# main.net
KiCad netlist of a schematic drawn in EAGLE
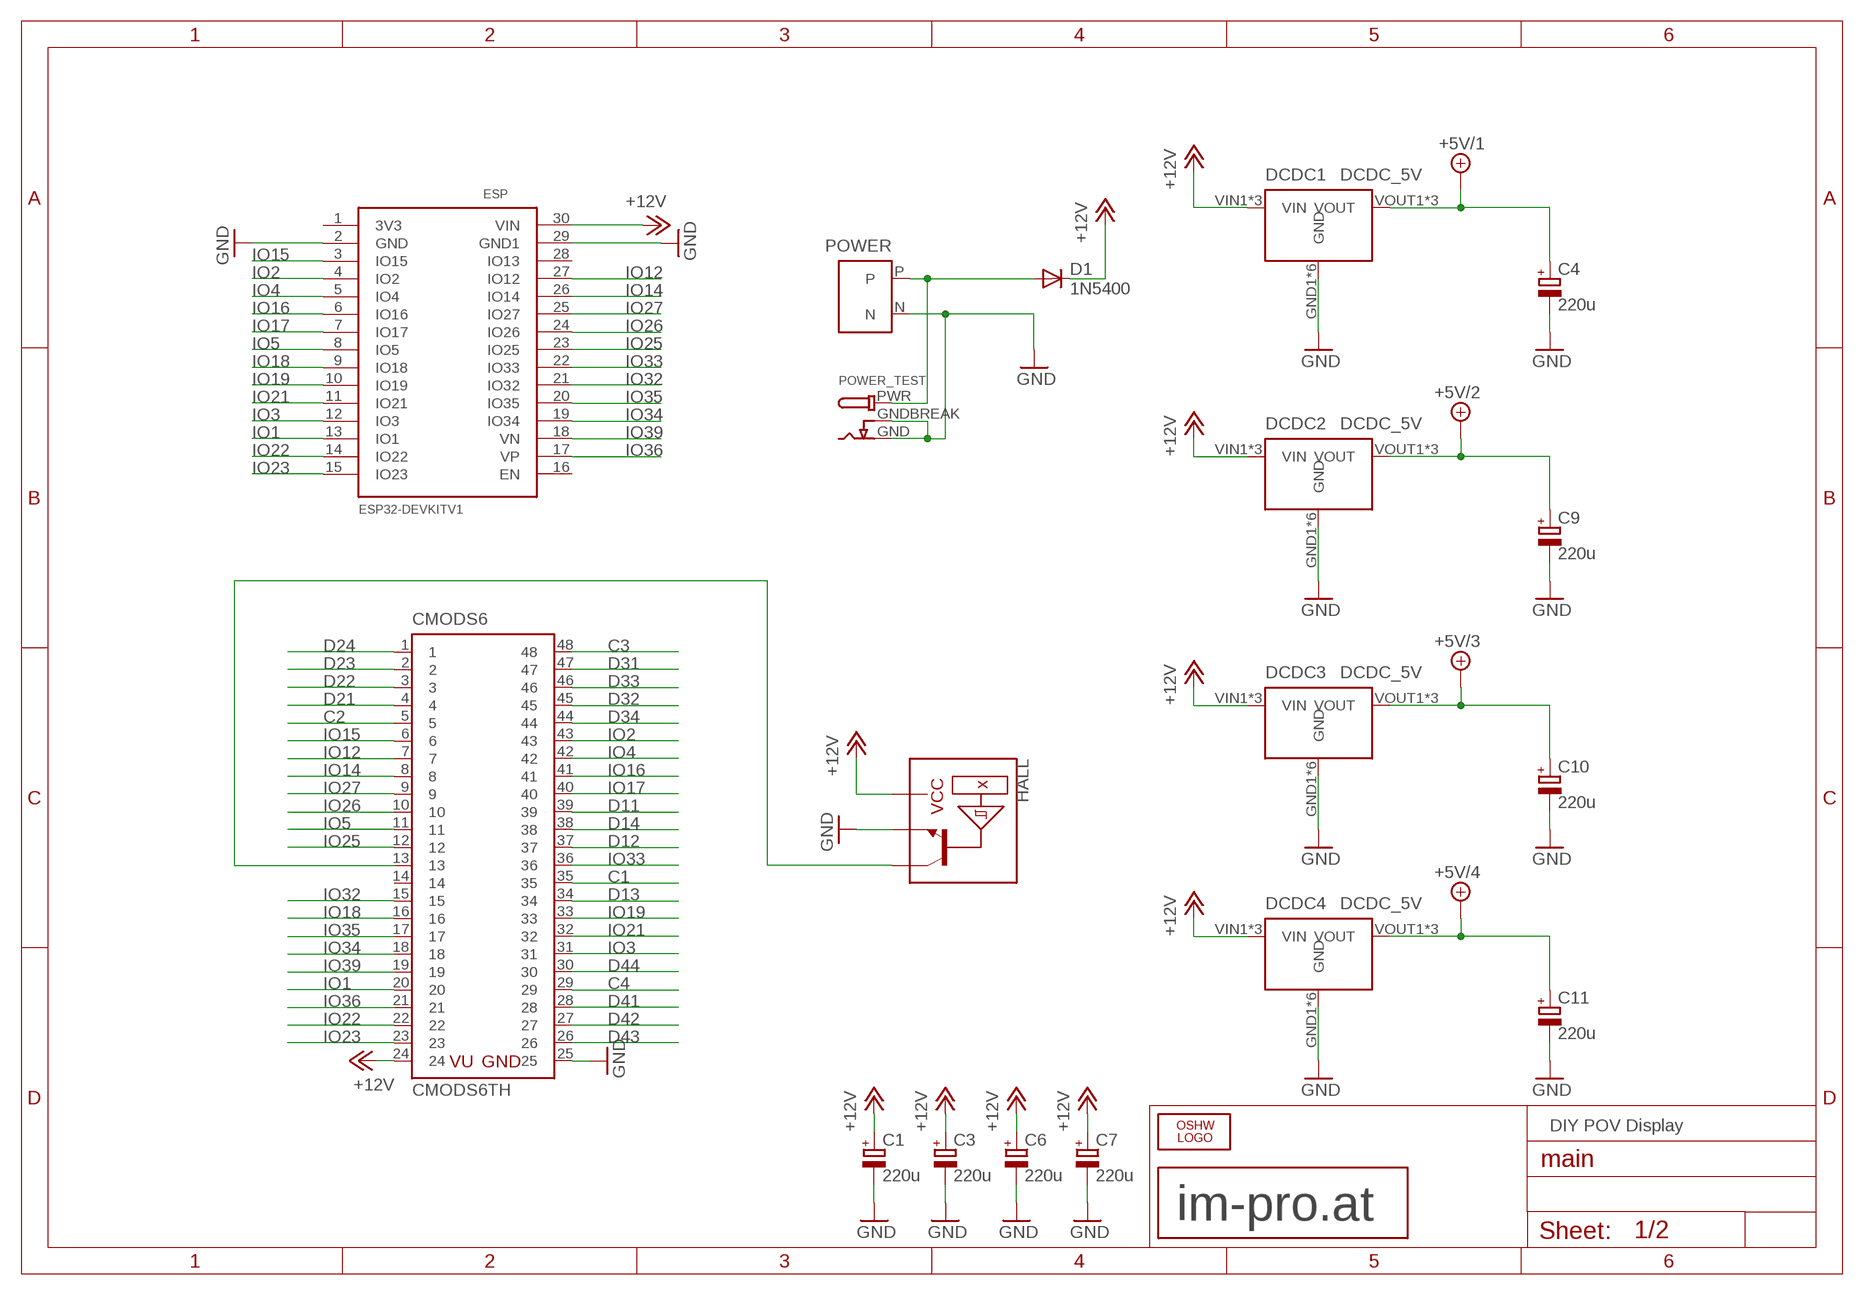
[diagram p0: schematic, sheet 1]
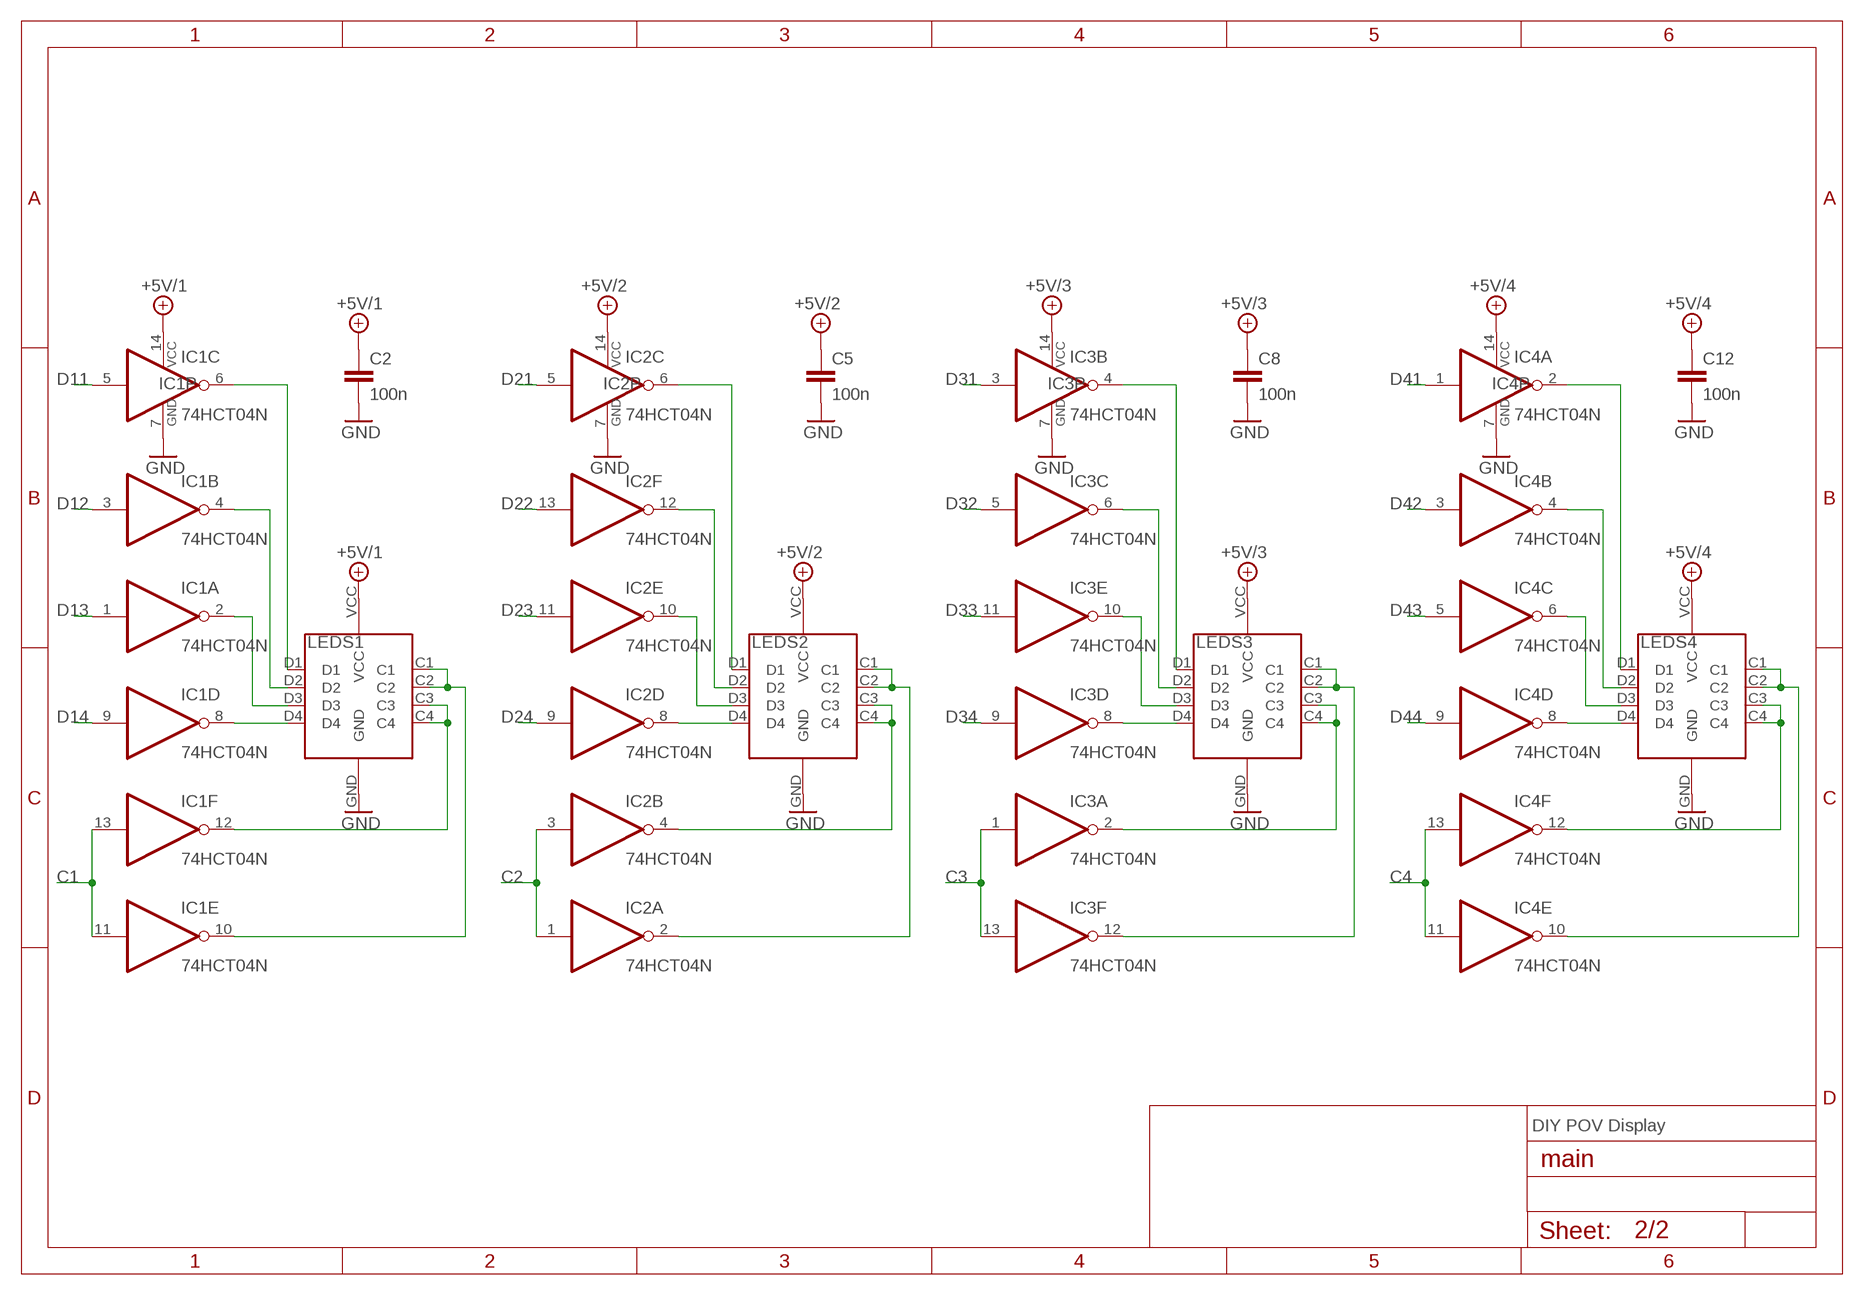
[diagram p1: schematic, sheet 2]

(export (version "E")
  (design (tool "Eeschema 10.0.6"))
  (components
    (comp (ref "C1")
      (value "220u")
      (footprint "eagle-import:E3,5-8")
      (libsource (lib "eagle-import") (part "CPOL-EUE3.5-8"))
    )
    (comp (ref "C3")
      (value "220u")
      (footprint "eagle-import:E3,5-8")
      (libsource (lib "eagle-import") (part "CPOL-EUE3.5-8"))
    )
    (comp (ref "C4")
      (value "220u")
      (footprint "eagle-import:E3,5-8")
      (libsource (lib "eagle-import") (part "CPOL-EUE3.5-8"))
    )
    (comp (ref "C6")
      (value "220u")
      (footprint "eagle-import:E3,5-8")
      (libsource (lib "eagle-import") (part "CPOL-EUE3.5-8"))
    )
    (comp (ref "C7")
      (value "220u")
      (footprint "eagle-import:E3,5-8")
      (libsource (lib "eagle-import") (part "CPOL-EUE3.5-8"))
    )
    (comp (ref "C9")
      (value "220u")
      (footprint "eagle-import:E3,5-8")
      (libsource (lib "eagle-import") (part "CPOL-EUE3.5-8"))
    )
    (comp (ref "C10")
      (value "220u")
      (footprint "eagle-import:E3,5-8")
      (libsource (lib "eagle-import") (part "CPOL-EUE3.5-8"))
    )
    (comp (ref "C11")
      (value "220u")
      (footprint "eagle-import:E3,5-8")
      (libsource (lib "eagle-import") (part "CPOL-EUE3.5-8"))
    )
    (comp (ref "CMODS6")
      (value "CMODS6TH")
      (footprint "eagle-import:DIL48")
      (libsource (lib "eagle-import") (part "CMODS6TH"))
    )
    (comp (ref "D1")
      (value "1N5400")
      (footprint "eagle-import:DO201-15")
      (libsource (lib "eagle-import") (part "1N5400"))
    )
    (comp (ref "DCDC1")
      (value "DCDC_5V")
      (footprint "eagle-import:DCDC")
      (libsource (lib "eagle-import") (part "DCDC_5V"))
    )
    (comp (ref "DCDC2")
      (value "DCDC_5V")
      (footprint "eagle-import:DCDC")
      (libsource (lib "eagle-import") (part "DCDC_5V"))
    )
    (comp (ref "DCDC3")
      (value "DCDC_5V")
      (footprint "eagle-import:DCDC")
      (libsource (lib "eagle-import") (part "DCDC_5V"))
    )
    (comp (ref "DCDC4")
      (value "DCDC_5V")
      (footprint "eagle-import:DCDC")
      (libsource (lib "eagle-import") (part "DCDC_5V"))
    )
    (comp (ref "ESP")
      (value "ESP32DEVKITV1")
      (footprint "eagle-import:ESP32-DEVKITV1")
      (libsource (lib "eagle-import") (part "ESP32DEVKITV1"))
    )
    (comp (ref "HALL")
      (value "HALL")
      (footprint "eagle-import:HALL")
      (libsource (lib "eagle-import") (part "HALL"))
    )
    (comp (ref "LOGO1")
      (value "OSHW_LOGO_FILLX0350-NT")
      (footprint "eagle-import:OSHW_FILLX350_NOTEXT")
      (libsource (lib "eagle-import") (part "OSHW_LOGO_FILLX0350-NT"))
    )
    (comp (ref "POWER")
      (value "TX30")
      (footprint "eagle-import:XT30")
      (libsource (lib "eagle-import") (part "TX30"))
    )
    (comp (ref "POWER_TEST")
      (value "DCBARRELPTH")
      (footprint "eagle-import:DCJACK_2MM_PTH")
      (libsource (lib "eagle-import") (part "DCBARRELPTH"))
    )
    (comp (ref "U$2")
      (value "LOGO20MM")
      (footprint "eagle-import:LOGO_20MM")
      (libsource (lib "eagle-import") (part "LOGO20MM"))
    )
    (comp (ref "C2")
      (value "100n")
      (footprint "eagle-import:C025_050-025X075")
      (libsource (lib "eagle-import") (part "C-EU025_050-025X075"))
    )
    (comp (ref "C5")
      (value "100n")
      (footprint "eagle-import:C025_050-025X075")
      (libsource (lib "eagle-import") (part "C-EU025_050-025X075"))
    )
    (comp (ref "C8")
      (value "100n")
      (footprint "eagle-import:C025_050-025X075")
      (libsource (lib "eagle-import") (part "C-EU025_050-025X075"))
    )
    (comp (ref "C12")
      (value "100n")
      (footprint "eagle-import:C025_050-025X075")
      (libsource (lib "eagle-import") (part "C-EU025_050-025X075"))
    )
    (comp (ref "IC1")
      (value "74HCT04N")
      (footprint "eagle-import:DIL14")
      (libsource (lib "eagle-import") (part "7404NHCT"))
    )
    (comp (ref "IC2")
      (value "74HCT04N")
      (footprint "eagle-import:DIL14")
      (libsource (lib "eagle-import") (part "7404NHCT"))
    )
    (comp (ref "IC3")
      (value "74HCT04N")
      (footprint "eagle-import:DIL14")
      (libsource (lib "eagle-import") (part "7404NHCT"))
    )
    (comp (ref "IC4")
      (value "74HCT04N")
      (footprint "eagle-import:DIL14")
      (libsource (lib "eagle-import") (part "7404NHCT"))
    )
    (comp (ref "LEDS1")
      (value "LEDCON")
      (footprint "eagle-import:LEDCON")
      (libsource (lib "eagle-import") (part "LEDCON"))
    )
    (comp (ref "LEDS2")
      (value "LEDCON")
      (footprint "eagle-import:LEDCON")
      (libsource (lib "eagle-import") (part "LEDCON"))
    )
    (comp (ref "LEDS3")
      (value "LEDCON")
      (footprint "eagle-import:LEDCON")
      (libsource (lib "eagle-import") (part "LEDCON"))
    )
    (comp (ref "LEDS4")
      (value "LEDCON")
      (footprint "eagle-import:LEDCON")
      (libsource (lib "eagle-import") (part "LEDCON"))
    )
  )
  (nets
    (net (code "1") (name "+5V{slash}1") (class "Default")
      (node (ref "C2") (pin "1") (pinfunction "1_1") (pintype "passive"))
      (node (ref "C4") (pin "+") (pinfunction "+_+") (pintype "passive"))
      (node (ref "DCDC1") (pin "VOUT1") (pinfunction "VOUT_VOUT1") (pintype "power_in"))
      (node (ref "DCDC1") (pin "VOUT2") (pinfunction "VOUT_VOUT2") (pintype "power_in"))
      (node (ref "DCDC1") (pin "VOUT3") (pinfunction "VOUT_VOUT3") (pintype "power_in"))
      (node (ref "IC1") (pin "14") (pinfunction "VCC_14") (pintype "power_in"))
      (node (ref "LEDS1") (pin "VCC") (pinfunction "VCC_VCC") (pintype "bidirectional"))
    )
    (net (code "2") (name "+5V{slash}2") (class "Default")
      (node (ref "C5") (pin "1") (pinfunction "1_1") (pintype "passive"))
      (node (ref "C9") (pin "+") (pinfunction "+_+") (pintype "passive"))
      (node (ref "DCDC2") (pin "VOUT1") (pinfunction "VOUT_VOUT1") (pintype "power_in"))
      (node (ref "DCDC2") (pin "VOUT2") (pinfunction "VOUT_VOUT2") (pintype "power_in"))
      (node (ref "DCDC2") (pin "VOUT3") (pinfunction "VOUT_VOUT3") (pintype "power_in"))
      (node (ref "IC2") (pin "14") (pinfunction "VCC_14") (pintype "power_in"))
      (node (ref "LEDS2") (pin "VCC") (pinfunction "VCC_VCC") (pintype "bidirectional"))
    )
    (net (code "3") (name "+5V{slash}3") (class "Default")
      (node (ref "C10") (pin "+") (pinfunction "+_+") (pintype "passive"))
      (node (ref "C8") (pin "1") (pinfunction "1_1") (pintype "passive"))
      (node (ref "DCDC3") (pin "VOUT1") (pinfunction "VOUT_VOUT1") (pintype "power_in"))
      (node (ref "DCDC3") (pin "VOUT2") (pinfunction "VOUT_VOUT2") (pintype "power_in"))
      (node (ref "DCDC3") (pin "VOUT3") (pinfunction "VOUT_VOUT3") (pintype "power_in"))
      (node (ref "IC3") (pin "14") (pinfunction "VCC_14") (pintype "power_in"))
      (node (ref "LEDS3") (pin "VCC") (pinfunction "VCC_VCC") (pintype "bidirectional"))
    )
    (net (code "4") (name "+5V{slash}4") (class "Default")
      (node (ref "C11") (pin "+") (pinfunction "+_+") (pintype "passive"))
      (node (ref "C12") (pin "1") (pinfunction "1_1") (pintype "passive"))
      (node (ref "DCDC4") (pin "VOUT1") (pinfunction "VOUT_VOUT1") (pintype "power_in"))
      (node (ref "DCDC4") (pin "VOUT2") (pinfunction "VOUT_VOUT2") (pintype "power_in"))
      (node (ref "DCDC4") (pin "VOUT3") (pinfunction "VOUT_VOUT3") (pintype "power_in"))
      (node (ref "IC4") (pin "14") (pinfunction "VCC_14") (pintype "power_in"))
      (node (ref "LEDS4") (pin "VCC") (pinfunction "VCC_VCC") (pintype "bidirectional"))
    )
    (net (code "5") (name "+12V") (class "Default")
      (node (ref "C1") (pin "+") (pinfunction "+_+") (pintype "passive"))
      (node (ref "C3") (pin "+") (pinfunction "+_+") (pintype "passive"))
      (node (ref "C6") (pin "+") (pinfunction "+_+") (pintype "passive"))
      (node (ref "C7") (pin "+") (pinfunction "+_+") (pintype "passive"))
      (node (ref "CMODS6") (pin "24") (pinfunction "24_24") (pintype "power_in"))
      (node (ref "D1") (pin "C") (pinfunction "C_C") (pintype "passive"))
      (node (ref "DCDC1") (pin "VIN1") (pinfunction "VIN_VIN1") (pintype "power_in"))
      (node (ref "DCDC1") (pin "VIN2") (pinfunction "VIN_VIN2") (pintype "power_in"))
      (node (ref "DCDC1") (pin "VIN3") (pinfunction "VIN_VIN3") (pintype "power_in"))
      (node (ref "DCDC2") (pin "VIN1") (pinfunction "VIN_VIN1") (pintype "power_in"))
      (node (ref "DCDC2") (pin "VIN2") (pinfunction "VIN_VIN2") (pintype "power_in"))
      (node (ref "DCDC2") (pin "VIN3") (pinfunction "VIN_VIN3") (pintype "power_in"))
      (node (ref "DCDC3") (pin "VIN1") (pinfunction "VIN_VIN1") (pintype "power_in"))
      (node (ref "DCDC3") (pin "VIN2") (pinfunction "VIN_VIN2") (pintype "power_in"))
      (node (ref "DCDC3") (pin "VIN3") (pinfunction "VIN_VIN3") (pintype "power_in"))
      (node (ref "DCDC4") (pin "VIN1") (pinfunction "VIN_VIN1") (pintype "power_in"))
      (node (ref "DCDC4") (pin "VIN2") (pinfunction "VIN_VIN2") (pintype "power_in"))
      (node (ref "DCDC4") (pin "VIN3") (pinfunction "VIN_VIN3") (pintype "power_in"))
      (node (ref "ESP") (pin "30") (pinfunction "VIN_30") (pintype "bidirectional"))
      (node (ref "HALL") (pin "VCC") (pinfunction "VCC_VCC") (pintype "power_in"))
    )
    (net (code "6") (name "C1") (class "Default")
      (node (ref "CMODS6") (pin "35") (pinfunction "35_35") (pintype "bidirectional"))
      (node (ref "IC1") (pin "11") (pinfunction "I_11") (pintype "input"))
      (node (ref "IC1") (pin "13") (pinfunction "I_13") (pintype "input"))
    )
    (net (code "7") (name "C2") (class "Default")
      (node (ref "CMODS6") (pin "5") (pinfunction "5_5") (pintype "bidirectional"))
      (node (ref "IC2") (pin "1") (pinfunction "I_1") (pintype "input"))
      (node (ref "IC2") (pin "3") (pinfunction "I_3") (pintype "input"))
    )
    (net (code "8") (name "C3") (class "Default")
      (node (ref "CMODS6") (pin "48") (pinfunction "48_48") (pintype "bidirectional"))
      (node (ref "IC3") (pin "1") (pinfunction "I_1") (pintype "input"))
      (node (ref "IC3") (pin "13") (pinfunction "I_13") (pintype "input"))
    )
    (net (code "9") (name "C4") (class "Default")
      (node (ref "CMODS6") (pin "29") (pinfunction "29_29") (pintype "bidirectional"))
      (node (ref "IC4") (pin "11") (pinfunction "I_11") (pintype "input"))
      (node (ref "IC4") (pin "13") (pinfunction "I_13") (pintype "input"))
    )
    (net (code "10") (name "D11") (class "Default")
      (node (ref "CMODS6") (pin "39") (pinfunction "39_39") (pintype "bidirectional"))
      (node (ref "IC1") (pin "5") (pinfunction "I_5") (pintype "input"))
    )
    (net (code "11") (name "D12") (class "Default")
      (node (ref "CMODS6") (pin "37") (pinfunction "37_37") (pintype "bidirectional"))
      (node (ref "IC1") (pin "3") (pinfunction "I_3") (pintype "input"))
    )
    (net (code "12") (name "D13") (class "Default")
      (node (ref "CMODS6") (pin "34") (pinfunction "34_34") (pintype "bidirectional"))
      (node (ref "IC1") (pin "1") (pinfunction "I_1") (pintype "input"))
    )
    (net (code "13") (name "D14") (class "Default")
      (node (ref "CMODS6") (pin "38") (pinfunction "38_38") (pintype "bidirectional"))
      (node (ref "IC1") (pin "9") (pinfunction "I_9") (pintype "input"))
    )
    (net (code "14") (name "D21") (class "Default")
      (node (ref "CMODS6") (pin "4") (pinfunction "4_4") (pintype "bidirectional"))
      (node (ref "IC2") (pin "5") (pinfunction "I_5") (pintype "input"))
    )
    (net (code "15") (name "D22") (class "Default")
      (node (ref "CMODS6") (pin "3") (pinfunction "3_3") (pintype "bidirectional"))
      (node (ref "IC2") (pin "13") (pinfunction "I_13") (pintype "input"))
    )
    (net (code "16") (name "D23") (class "Default")
      (node (ref "CMODS6") (pin "2") (pinfunction "2_2") (pintype "bidirectional"))
      (node (ref "IC2") (pin "11") (pinfunction "I_11") (pintype "input"))
    )
    (net (code "17") (name "D24") (class "Default")
      (node (ref "CMODS6") (pin "1") (pinfunction "1_1") (pintype "bidirectional"))
      (node (ref "IC2") (pin "9") (pinfunction "I_9") (pintype "input"))
    )
    (net (code "18") (name "D31") (class "Default")
      (node (ref "CMODS6") (pin "47") (pinfunction "47_47") (pintype "bidirectional"))
      (node (ref "IC3") (pin "3") (pinfunction "I_3") (pintype "input"))
    )
    (net (code "19") (name "D32") (class "Default")
      (node (ref "CMODS6") (pin "45") (pinfunction "45_45") (pintype "bidirectional"))
      (node (ref "IC3") (pin "5") (pinfunction "I_5") (pintype "input"))
    )
    (net (code "20") (name "D33") (class "Default")
      (node (ref "CMODS6") (pin "46") (pinfunction "46_46") (pintype "bidirectional"))
      (node (ref "IC3") (pin "11") (pinfunction "I_11") (pintype "input"))
    )
    (net (code "21") (name "D34") (class "Default")
      (node (ref "CMODS6") (pin "44") (pinfunction "44_44") (pintype "bidirectional"))
      (node (ref "IC3") (pin "9") (pinfunction "I_9") (pintype "input"))
    )
    (net (code "22") (name "D41") (class "Default")
      (node (ref "CMODS6") (pin "28") (pinfunction "28_28") (pintype "bidirectional"))
      (node (ref "IC4") (pin "1") (pinfunction "I_1") (pintype "input"))
    )
    (net (code "23") (name "D42") (class "Default")
      (node (ref "CMODS6") (pin "27") (pinfunction "27_27") (pintype "bidirectional"))
      (node (ref "IC4") (pin "3") (pinfunction "I_3") (pintype "input"))
    )
    (net (code "24") (name "D43") (class "Default")
      (node (ref "CMODS6") (pin "26") (pinfunction "26_26") (pintype "bidirectional"))
      (node (ref "IC4") (pin "5") (pinfunction "I_5") (pintype "input"))
    )
    (net (code "25") (name "D44") (class "Default")
      (node (ref "CMODS6") (pin "30") (pinfunction "30_30") (pintype "bidirectional"))
      (node (ref "IC4") (pin "9") (pinfunction "I_9") (pintype "input"))
    )
    (net (code "26") (name "GND") (class "Default")
      (node (ref "C1") (pin "-") (pinfunction "-_-") (pintype "passive"))
      (node (ref "C10") (pin "-") (pinfunction "-_-") (pintype "passive"))
      (node (ref "C11") (pin "-") (pinfunction "-_-") (pintype "passive"))
      (node (ref "C12") (pin "2") (pinfunction "2_2") (pintype "passive"))
      (node (ref "C12") (pin "3") (pinfunction "2_3") (pintype "passive"))
      (node (ref "C2") (pin "2") (pinfunction "2_2") (pintype "passive"))
      (node (ref "C2") (pin "3") (pinfunction "2_3") (pintype "passive"))
      (node (ref "C3") (pin "-") (pinfunction "-_-") (pintype "passive"))
      (node (ref "C4") (pin "-") (pinfunction "-_-") (pintype "passive"))
      (node (ref "C5") (pin "2") (pinfunction "2_2") (pintype "passive"))
      (node (ref "C5") (pin "3") (pinfunction "2_3") (pintype "passive"))
      (node (ref "C6") (pin "-") (pinfunction "-_-") (pintype "passive"))
      (node (ref "C7") (pin "-") (pinfunction "-_-") (pintype "passive"))
      (node (ref "C8") (pin "2") (pinfunction "2_2") (pintype "passive"))
      (node (ref "C8") (pin "3") (pinfunction "2_3") (pintype "passive"))
      (node (ref "C9") (pin "-") (pinfunction "-_-") (pintype "passive"))
      (node (ref "CMODS6") (pin "25") (pinfunction "25_25") (pintype "power_in"))
      (node (ref "DCDC1") (pin "GND1") (pinfunction "GND_GND1") (pintype "power_in"))
      (node (ref "DCDC1") (pin "GND2") (pinfunction "GND_GND2") (pintype "power_in"))
      (node (ref "DCDC1") (pin "GND3") (pinfunction "GND_GND3") (pintype "power_in"))
      (node (ref "DCDC1") (pin "GND4") (pinfunction "GND_GND4") (pintype "power_in"))
      (node (ref "DCDC1") (pin "GND5") (pinfunction "GND_GND5") (pintype "power_in"))
      (node (ref "DCDC1") (pin "GND6") (pinfunction "GND_GND6") (pintype "power_in"))
      (node (ref "DCDC2") (pin "GND1") (pinfunction "GND_GND1") (pintype "power_in"))
      (node (ref "DCDC2") (pin "GND2") (pinfunction "GND_GND2") (pintype "power_in"))
      (node (ref "DCDC2") (pin "GND3") (pinfunction "GND_GND3") (pintype "power_in"))
      (node (ref "DCDC2") (pin "GND4") (pinfunction "GND_GND4") (pintype "power_in"))
      (node (ref "DCDC2") (pin "GND5") (pinfunction "GND_GND5") (pintype "power_in"))
      (node (ref "DCDC2") (pin "GND6") (pinfunction "GND_GND6") (pintype "power_in"))
      (node (ref "DCDC3") (pin "GND1") (pinfunction "GND_GND1") (pintype "power_in"))
      (node (ref "DCDC3") (pin "GND2") (pinfunction "GND_GND2") (pintype "power_in"))
      (node (ref "DCDC3") (pin "GND3") (pinfunction "GND_GND3") (pintype "power_in"))
      (node (ref "DCDC3") (pin "GND4") (pinfunction "GND_GND4") (pintype "power_in"))
      (node (ref "DCDC3") (pin "GND5") (pinfunction "GND_GND5") (pintype "power_in"))
      (node (ref "DCDC3") (pin "GND6") (pinfunction "GND_GND6") (pintype "power_in"))
      (node (ref "DCDC4") (pin "GND1") (pinfunction "GND_GND1") (pintype "power_in"))
      (node (ref "DCDC4") (pin "GND2") (pinfunction "GND_GND2") (pintype "power_in"))
      (node (ref "DCDC4") (pin "GND3") (pinfunction "GND_GND3") (pintype "power_in"))
      (node (ref "DCDC4") (pin "GND4") (pinfunction "GND_GND4") (pintype "power_in"))
      (node (ref "DCDC4") (pin "GND5") (pinfunction "GND_GND5") (pintype "power_in"))
      (node (ref "DCDC4") (pin "GND6") (pinfunction "GND_GND6") (pintype "power_in"))
      (node (ref "ESP") (pin "2") (pinfunction "GND_2") (pintype "bidirectional"))
      (node (ref "ESP") (pin "29") (pinfunction "GND1_29") (pintype "bidirectional"))
      (node (ref "HALL") (pin "GND") (pinfunction "GND_GND") (pintype "power_in"))
      (node (ref "IC1") (pin "7") (pinfunction "GND_7") (pintype "power_in"))
      (node (ref "IC2") (pin "7") (pinfunction "GND_7") (pintype "power_in"))
      (node (ref "IC3") (pin "7") (pinfunction "GND_7") (pintype "power_in"))
      (node (ref "IC4") (pin "7") (pinfunction "GND_7") (pintype "power_in"))
      (node (ref "LEDS1") (pin "GND") (pinfunction "GND_GND") (pintype "bidirectional"))
      (node (ref "LEDS2") (pin "GND") (pinfunction "GND_GND") (pintype "bidirectional"))
      (node (ref "LEDS3") (pin "GND") (pinfunction "GND_GND") (pintype "bidirectional"))
      (node (ref "LEDS4") (pin "GND") (pinfunction "GND_GND") (pintype "bidirectional"))
      (node (ref "POWER") (pin "N") (pinfunction "N_N") (pintype "power_in"))
      (node (ref "POWER_TEST") (pin "GND") (pinfunction "GND_GND") (pintype "power_in"))
      (node (ref "POWER_TEST") (pin "GNDBREAK") (pinfunction "GNDBREAK_GNDBREAK") (pintype "power_in"))
    )
    (net (code "27") (name "IO1") (class "Default")
      (node (ref "CMODS6") (pin "20") (pinfunction "20_20") (pintype "bidirectional"))
      (node (ref "ESP") (pin "13") (pinfunction "IO1_13") (pintype "bidirectional"))
    )
    (net (code "28") (name "IO2") (class "Default")
      (node (ref "CMODS6") (pin "43") (pinfunction "43_43") (pintype "bidirectional"))
      (node (ref "ESP") (pin "4") (pinfunction "IO2_4") (pintype "bidirectional"))
    )
    (net (code "29") (name "IO3") (class "Default")
      (node (ref "CMODS6") (pin "31") (pinfunction "31_31") (pintype "bidirectional"))
      (node (ref "ESP") (pin "12") (pinfunction "IO3_12") (pintype "bidirectional"))
    )
    (net (code "30") (name "IO4") (class "Default")
      (node (ref "CMODS6") (pin "42") (pinfunction "42_42") (pintype "bidirectional"))
      (node (ref "ESP") (pin "5") (pinfunction "IO4_5") (pintype "bidirectional"))
    )
    (net (code "31") (name "IO5") (class "Default")
      (node (ref "CMODS6") (pin "11") (pinfunction "11_11") (pintype "bidirectional"))
      (node (ref "ESP") (pin "8") (pinfunction "IO5_8") (pintype "bidirectional"))
    )
    (net (code "32") (name "IO12") (class "Default")
      (node (ref "CMODS6") (pin "7") (pinfunction "7_7") (pintype "bidirectional"))
      (node (ref "ESP") (pin "27") (pinfunction "IO12_27") (pintype "bidirectional"))
    )
    (net (code "33") (name "IO14") (class "Default")
      (node (ref "CMODS6") (pin "8") (pinfunction "8_8") (pintype "bidirectional"))
      (node (ref "ESP") (pin "26") (pinfunction "IO14_26") (pintype "bidirectional"))
    )
    (net (code "34") (name "IO15") (class "Default")
      (node (ref "CMODS6") (pin "6") (pinfunction "6_6") (pintype "bidirectional"))
      (node (ref "ESP") (pin "3") (pinfunction "IO15_3") (pintype "bidirectional"))
    )
    (net (code "35") (name "IO16") (class "Default")
      (node (ref "CMODS6") (pin "41") (pinfunction "41_41") (pintype "bidirectional"))
      (node (ref "ESP") (pin "6") (pinfunction "IO16_6") (pintype "bidirectional"))
    )
    (net (code "36") (name "IO17") (class "Default")
      (node (ref "CMODS6") (pin "40") (pinfunction "40_40") (pintype "bidirectional"))
      (node (ref "ESP") (pin "7") (pinfunction "IO17_7") (pintype "bidirectional"))
    )
    (net (code "37") (name "IO18") (class "Default")
      (node (ref "CMODS6") (pin "16") (pinfunction "16_16") (pintype "bidirectional"))
      (node (ref "ESP") (pin "9") (pinfunction "IO18_9") (pintype "bidirectional"))
    )
    (net (code "38") (name "IO19") (class "Default")
      (node (ref "CMODS6") (pin "33") (pinfunction "33_33") (pintype "bidirectional"))
      (node (ref "ESP") (pin "10") (pinfunction "IO19_10") (pintype "bidirectional"))
    )
    (net (code "39") (name "IO21") (class "Default")
      (node (ref "CMODS6") (pin "32") (pinfunction "32_32") (pintype "bidirectional"))
      (node (ref "ESP") (pin "11") (pinfunction "IO21_11") (pintype "bidirectional"))
    )
    (net (code "40") (name "IO22") (class "Default")
      (node (ref "CMODS6") (pin "22") (pinfunction "22_22") (pintype "bidirectional"))
      (node (ref "ESP") (pin "14") (pinfunction "IO22_14") (pintype "bidirectional"))
    )
    (net (code "41") (name "IO23") (class "Default")
      (node (ref "CMODS6") (pin "23") (pinfunction "23_23") (pintype "bidirectional"))
      (node (ref "ESP") (pin "15") (pinfunction "IO23_15") (pintype "bidirectional"))
    )
    (net (code "42") (name "IO25") (class "Default")
      (node (ref "CMODS6") (pin "12") (pinfunction "12_12") (pintype "bidirectional"))
      (node (ref "ESP") (pin "23") (pinfunction "IO25_23") (pintype "bidirectional"))
    )
    (net (code "43") (name "IO26") (class "Default")
      (node (ref "CMODS6") (pin "10") (pinfunction "10_10") (pintype "bidirectional"))
      (node (ref "ESP") (pin "24") (pinfunction "IO26_24") (pintype "bidirectional"))
    )
    (net (code "44") (name "IO27") (class "Default")
      (node (ref "CMODS6") (pin "9") (pinfunction "9_9") (pintype "bidirectional"))
      (node (ref "ESP") (pin "25") (pinfunction "IO27_25") (pintype "bidirectional"))
    )
    (net (code "45") (name "IO32") (class "Default")
      (node (ref "CMODS6") (pin "15") (pinfunction "15_15") (pintype "bidirectional"))
      (node (ref "ESP") (pin "21") (pinfunction "IO32_21") (pintype "bidirectional"))
    )
    (net (code "46") (name "IO33") (class "Default")
      (node (ref "CMODS6") (pin "36") (pinfunction "36_36") (pintype "bidirectional"))
      (node (ref "ESP") (pin "22") (pinfunction "IO33_22") (pintype "bidirectional"))
    )
    (net (code "47") (name "IO34") (class "Default")
      (node (ref "CMODS6") (pin "18") (pinfunction "18_18") (pintype "bidirectional"))
      (node (ref "ESP") (pin "19") (pinfunction "IO34_19") (pintype "bidirectional"))
    )
    (net (code "48") (name "IO35") (class "Default")
      (node (ref "CMODS6") (pin "17") (pinfunction "17_17") (pintype "bidirectional"))
      (node (ref "ESP") (pin "20") (pinfunction "IO35_20") (pintype "bidirectional"))
    )
    (net (code "49") (name "IO36") (class "Default")
      (node (ref "CMODS6") (pin "21") (pinfunction "21_21") (pintype "bidirectional"))
      (node (ref "ESP") (pin "17") (pinfunction "VP_17") (pintype "bidirectional"))
    )
    (net (code "50") (name "IO39") (class "Default")
      (node (ref "CMODS6") (pin "19") (pinfunction "19_19") (pintype "bidirectional"))
      (node (ref "ESP") (pin "18") (pinfunction "VN_18") (pintype "bidirectional"))
    )
    (net (code "51") (name "Net-(CMODS6-Pad13)") (class "Default")
      (node (ref "CMODS6") (pin "13") (pinfunction "13_13") (pintype "bidirectional"))
      (node (ref "HALL") (pin "OUT") (pinfunction "OUT_OUT") (pintype "open_collector"))
    )
    (net (code "52") (name "Net-(D1-PadA)") (class "Default")
      (node (ref "D1") (pin "A") (pinfunction "A_A") (pintype "passive"))
      (node (ref "POWER") (pin "P") (pinfunction "P_P") (pintype "power_in"))
      (node (ref "POWER_TEST") (pin "PWR") (pinfunction "PWR_PWR") (pintype "power_in"))
    )
    (net (code "53") (name "Net-(IC1A-O)") (class "Default")
      (node (ref "IC1") (pin "2") (pinfunction "O_2") (pintype "output"))
      (node (ref "LEDS1") (pin "D3") (pinfunction "D3_D3") (pintype "power_in"))
    )
    (net (code "54") (name "Net-(IC1B-O)") (class "Default")
      (node (ref "IC1") (pin "4") (pinfunction "O_4") (pintype "output"))
      (node (ref "LEDS1") (pin "D2") (pinfunction "D2_D2") (pintype "power_in"))
    )
    (net (code "55") (name "Net-(IC1C-O)") (class "Default")
      (node (ref "IC1") (pin "6") (pinfunction "O_6") (pintype "output"))
      (node (ref "LEDS1") (pin "D1") (pinfunction "D1_D1") (pintype "power_in"))
    )
    (net (code "56") (name "Net-(IC1D-O)") (class "Default")
      (node (ref "IC1") (pin "8") (pinfunction "O_8") (pintype "output"))
      (node (ref "LEDS1") (pin "D4") (pinfunction "D4_D4") (pintype "power_in"))
    )
    (net (code "57") (name "Net-(IC1E-O)") (class "Default")
      (node (ref "IC1") (pin "10") (pinfunction "O_10") (pintype "output"))
      (node (ref "LEDS1") (pin "C1") (pinfunction "C1_C1") (pintype "power_in"))
      (node (ref "LEDS1") (pin "C2") (pinfunction "C2_C2") (pintype "power_in"))
    )
    (net (code "58") (name "Net-(IC1F-O)") (class "Default")
      (node (ref "IC1") (pin "12") (pinfunction "O_12") (pintype "output"))
      (node (ref "LEDS1") (pin "C3") (pinfunction "C3_C3") (pintype "power_in"))
      (node (ref "LEDS1") (pin "C4") (pinfunction "C4_C4") (pintype "power_in"))
    )
    (net (code "59") (name "Net-(IC2A-O)") (class "Default")
      (node (ref "IC2") (pin "2") (pinfunction "O_2") (pintype "output"))
      (node (ref "LEDS2") (pin "C1") (pinfunction "C1_C1") (pintype "power_in"))
      (node (ref "LEDS2") (pin "C2") (pinfunction "C2_C2") (pintype "power_in"))
    )
    (net (code "60") (name "Net-(IC2B-O)") (class "Default")
      (node (ref "IC2") (pin "4") (pinfunction "O_4") (pintype "output"))
      (node (ref "LEDS2") (pin "C3") (pinfunction "C3_C3") (pintype "power_in"))
      (node (ref "LEDS2") (pin "C4") (pinfunction "C4_C4") (pintype "power_in"))
    )
    (net (code "61") (name "Net-(IC2C-O)") (class "Default")
      (node (ref "IC2") (pin "6") (pinfunction "O_6") (pintype "output"))
      (node (ref "LEDS2") (pin "D1") (pinfunction "D1_D1") (pintype "power_in"))
    )
    (net (code "62") (name "Net-(IC2D-O)") (class "Default")
      (node (ref "IC2") (pin "8") (pinfunction "O_8") (pintype "output"))
      (node (ref "LEDS2") (pin "D4") (pinfunction "D4_D4") (pintype "power_in"))
    )
    (net (code "63") (name "Net-(IC2E-O)") (class "Default")
      (node (ref "IC2") (pin "10") (pinfunction "O_10") (pintype "output"))
      (node (ref "LEDS2") (pin "D3") (pinfunction "D3_D3") (pintype "power_in"))
    )
    (net (code "64") (name "Net-(IC2F-O)") (class "Default")
      (node (ref "IC2") (pin "12") (pinfunction "O_12") (pintype "output"))
      (node (ref "LEDS2") (pin "D2") (pinfunction "D2_D2") (pintype "power_in"))
    )
    (net (code "65") (name "Net-(IC3A-O)") (class "Default")
      (node (ref "IC3") (pin "2") (pinfunction "O_2") (pintype "output"))
      (node (ref "LEDS3") (pin "C3") (pinfunction "C3_C3") (pintype "power_in"))
      (node (ref "LEDS3") (pin "C4") (pinfunction "C4_C4") (pintype "power_in"))
    )
    (net (code "66") (name "Net-(IC3B-O)") (class "Default")
      (node (ref "IC3") (pin "4") (pinfunction "O_4") (pintype "output"))
      (node (ref "LEDS3") (pin "D1") (pinfunction "D1_D1") (pintype "power_in"))
    )
    (net (code "67") (name "Net-(IC3C-O)") (class "Default")
      (node (ref "IC3") (pin "6") (pinfunction "O_6") (pintype "output"))
      (node (ref "LEDS3") (pin "D2") (pinfunction "D2_D2") (pintype "power_in"))
    )
    (net (code "68") (name "Net-(IC3D-O)") (class "Default")
      (node (ref "IC3") (pin "8") (pinfunction "O_8") (pintype "output"))
      (node (ref "LEDS3") (pin "D4") (pinfunction "D4_D4") (pintype "power_in"))
    )
    (net (code "69") (name "Net-(IC3E-O)") (class "Default")
      (node (ref "IC3") (pin "10") (pinfunction "O_10") (pintype "output"))
      (node (ref "LEDS3") (pin "D3") (pinfunction "D3_D3") (pintype "power_in"))
    )
    (net (code "70") (name "Net-(IC3F-O)") (class "Default")
      (node (ref "IC3") (pin "12") (pinfunction "O_12") (pintype "output"))
      (node (ref "LEDS3") (pin "C1") (pinfunction "C1_C1") (pintype "power_in"))
      (node (ref "LEDS3") (pin "C2") (pinfunction "C2_C2") (pintype "power_in"))
    )
    (net (code "71") (name "Net-(IC4A-O)") (class "Default")
      (node (ref "IC4") (pin "2") (pinfunction "O_2") (pintype "output"))
      (node (ref "LEDS4") (pin "D1") (pinfunction "D1_D1") (pintype "power_in"))
    )
    (net (code "72") (name "Net-(IC4B-O)") (class "Default")
      (node (ref "IC4") (pin "4") (pinfunction "O_4") (pintype "output"))
      (node (ref "LEDS4") (pin "D2") (pinfunction "D2_D2") (pintype "power_in"))
    )
    (net (code "73") (name "Net-(IC4C-O)") (class "Default")
      (node (ref "IC4") (pin "6") (pinfunction "O_6") (pintype "output"))
      (node (ref "LEDS4") (pin "D3") (pinfunction "D3_D3") (pintype "power_in"))
    )
    (net (code "74") (name "Net-(IC4D-O)") (class "Default")
      (node (ref "IC4") (pin "8") (pinfunction "O_8") (pintype "output"))
      (node (ref "LEDS4") (pin "D4") (pinfunction "D4_D4") (pintype "power_in"))
    )
    (net (code "75") (name "Net-(IC4E-O)") (class "Default")
      (node (ref "IC4") (pin "10") (pinfunction "O_10") (pintype "output"))
      (node (ref "LEDS4") (pin "C1") (pinfunction "C1_C1") (pintype "power_in"))
      (node (ref "LEDS4") (pin "C2") (pinfunction "C2_C2") (pintype "power_in"))
    )
    (net (code "76") (name "Net-(IC4F-O)") (class "Default")
      (node (ref "IC4") (pin "12") (pinfunction "O_12") (pintype "output"))
      (node (ref "LEDS4") (pin "C3") (pinfunction "C3_C3") (pintype "power_in"))
      (node (ref "LEDS4") (pin "C4") (pinfunction "C4_C4") (pintype "power_in"))
    )
    (net (code "77") (name "unconnected-(CMODS6-Pad14)") (class "Default")
      (node (ref "CMODS6") (pin "14") (pinfunction "14_14") (pintype "bidirectional"))
    )
    (net (code "78") (name "unconnected-(ESP-3V3-Pad1)") (class "Default")
      (node (ref "ESP") (pin "1") (pinfunction "3V3_1") (pintype "bidirectional"))
    )
    (net (code "79") (name "unconnected-(ESP-EN-Pad16)") (class "Default")
      (node (ref "ESP") (pin "16") (pinfunction "EN_16") (pintype "bidirectional"))
    )
    (net (code "80") (name "unconnected-(ESP-IO13-Pad28)") (class "Default")
      (node (ref "ESP") (pin "28") (pinfunction "IO13_28") (pintype "bidirectional"))
    )
  )
)
